# m2_to_apple.net
KiCad netlist of a schematic drawn in EAGLE
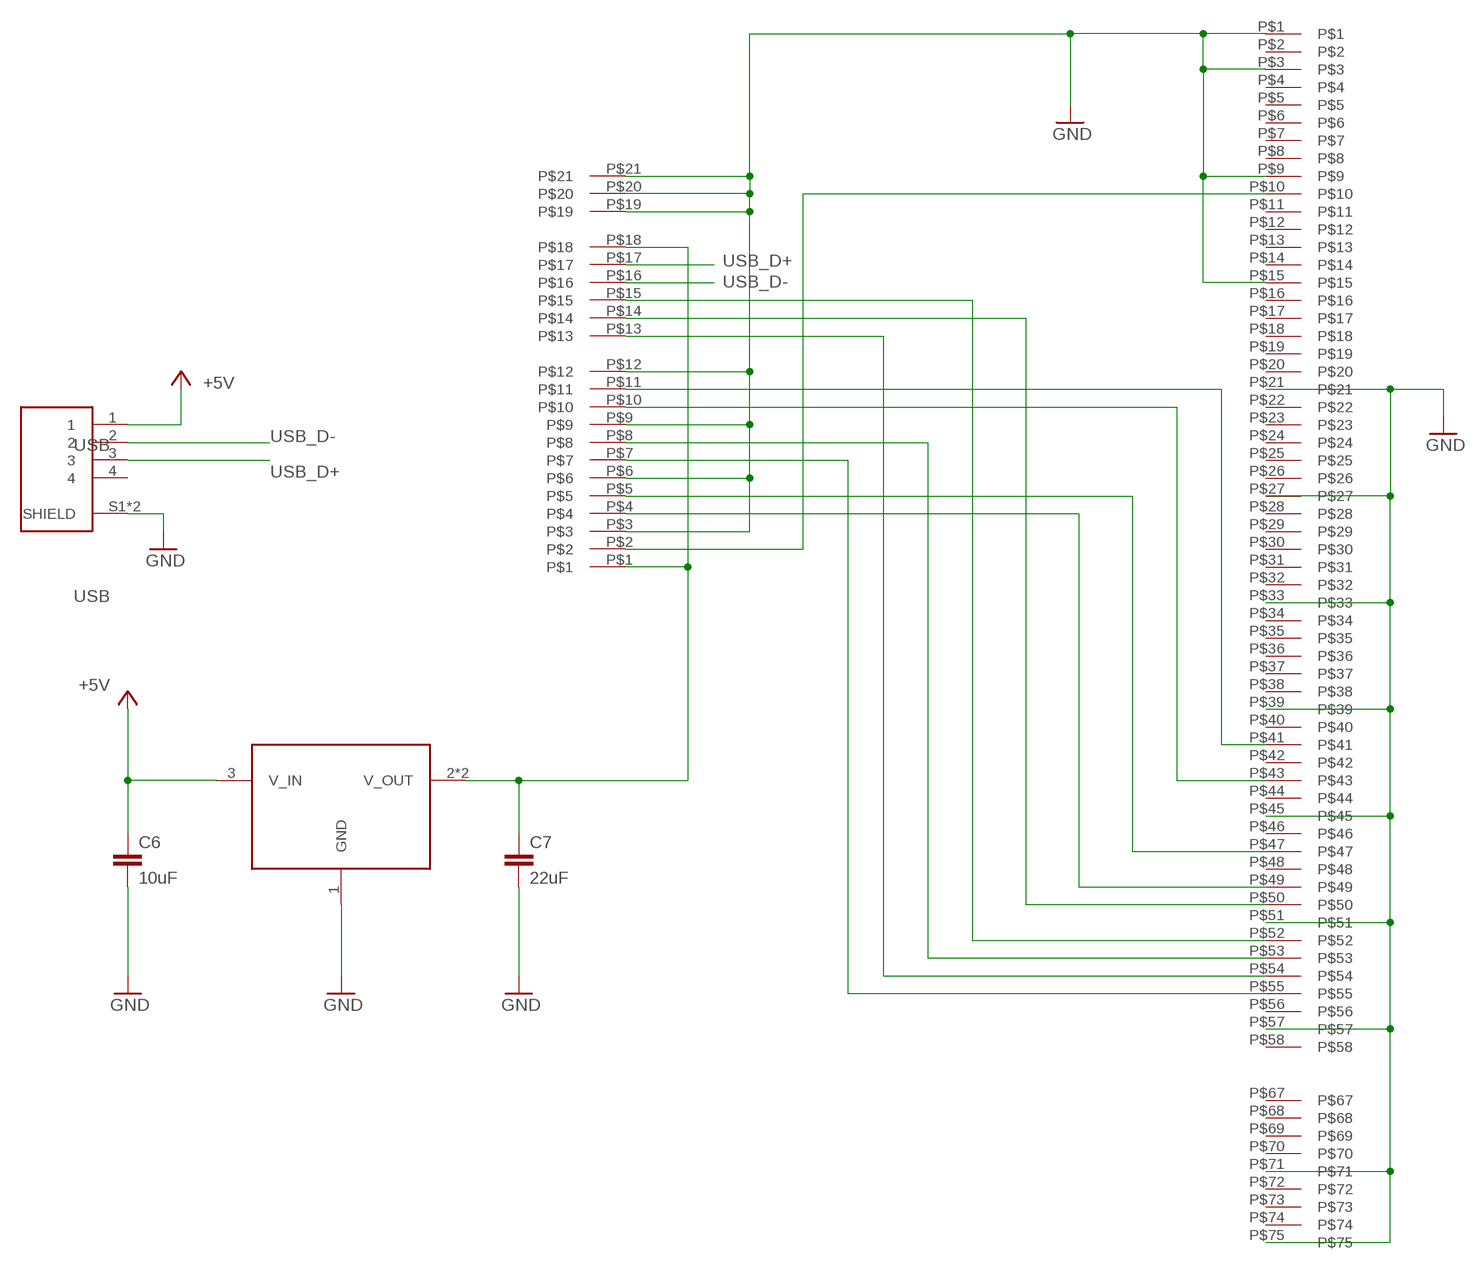
[diagram p0: schematic, sheet 1]

(export (version "E")
  (design (tool "Eeschema 10.0.6"))
  (components
    (comp (ref "C6")
      (value "10uF")
      (footprint "eagle-import:CAP_0603")
      (fields
        (field (name "DIGIKEY_PART_NUMBER") "399-7814-2-ND")
        (field (name "MANUFACTURER") "KEMET")
        (field (name "MPN") "C0603C100C5GACTU")
        (field (name "CREATED_BY") "PCBLayout.com")
      )
      (libsource (lib "eagle-import") (part "C0603C100C5GACTU"))
    )
    (comp (ref "C7")
      (value "22uF")
      (footprint "eagle-import:CAP_0603")
      (fields
        (field (name "DIGIKEY_PART_NUMBER") "399-7814-2-ND")
        (field (name "MANUFACTURER") "KEMET")
        (field (name "MPN") "C0603C100C5GACTU")
        (field (name "CREATED_BY") "PCBLayout.com")
      )
      (libsource (lib "eagle-import") (part "C0603C100C5GACTU"))
    )
    (comp (ref "U$1")
      (value "APPLE-WIFI")
      (footprint "eagle-import:APPLE_WIFI")
      (libsource (lib "eagle-import") (part "APPLE-WIFI"))
    )
    (comp (ref "U$2")
      (value "M.2_KEY_MSMD")
      (footprint "eagle-import:M.2_KEY_M")
      (libsource (lib "eagle-import") (part "M.2_KEY_MSMD"))
    )
    (comp (ref "U$3")
      (value "LM1117")
      (footprint "eagle-import:SOT223")
      (libsource (lib "eagle-import") (part "LM1117"))
    )
    (comp (ref "USB")
      (value "USB")
      (footprint "eagle-import:JST_1MM_4PINS")
      (libsource (lib "eagle-import") (part "JST_1MM_4PINS"))
    )
  )
  (nets
    (net (code "1") (name "+5V") (class "Default")
      (node (ref "C6") (pin "1") (pinfunction "1_1") (pintype "passive"))
      (node (ref "U$3") (pin "3") (pinfunction "V_IN_3") (pintype "input"))
      (node (ref "USB") (pin "1") (pinfunction "1_1") (pintype "passive"))
    )
    (net (code "2") (name "/USB_D+") (class "Default")
      (node (ref "U$1") (pin "P$17") (pinfunction "P$17_P$17") (pintype "bidirectional"))
      (node (ref "USB") (pin "3") (pinfunction "3_3") (pintype "passive"))
    )
    (net (code "3") (name "/USB_D-") (class "Default")
      (node (ref "U$1") (pin "P$16") (pinfunction "P$16_P$16") (pintype "bidirectional"))
      (node (ref "USB") (pin "2") (pinfunction "2_2") (pintype "passive"))
    )
    (net (code "4") (name "GND") (class "Default")
      (node (ref "C6") (pin "2") (pinfunction "2_2") (pintype "passive"))
      (node (ref "C7") (pin "2") (pinfunction "2_2") (pintype "passive"))
      (node (ref "U$1") (pin "P$12") (pinfunction "P$12_P$12") (pintype "bidirectional"))
      (node (ref "U$1") (pin "P$19") (pinfunction "P$19_P$19") (pintype "bidirectional"))
      (node (ref "U$1") (pin "P$20") (pinfunction "P$20_P$20") (pintype "bidirectional"))
      (node (ref "U$1") (pin "P$21") (pinfunction "P$21_P$21") (pintype "bidirectional"))
      (node (ref "U$1") (pin "P$3") (pinfunction "P$3_P$3") (pintype "bidirectional"))
      (node (ref "U$1") (pin "P$6") (pinfunction "P$6_P$6") (pintype "bidirectional"))
      (node (ref "U$1") (pin "P$9") (pinfunction "P$9_P$9") (pintype "bidirectional"))
      (node (ref "U$2") (pin "P$1") (pinfunction "P$1_P$1") (pintype "bidirectional"))
      (node (ref "U$2") (pin "P$15") (pinfunction "P$15_P$15") (pintype "bidirectional"))
      (node (ref "U$2") (pin "P$21") (pinfunction "P$21_P$21") (pintype "bidirectional"))
      (node (ref "U$2") (pin "P$27") (pinfunction "P$27_P$27") (pintype "bidirectional"))
      (node (ref "U$2") (pin "P$3") (pinfunction "P$3_P$3") (pintype "bidirectional"))
      (node (ref "U$2") (pin "P$33") (pinfunction "P$33_P$33") (pintype "bidirectional"))
      (node (ref "U$2") (pin "P$39") (pinfunction "P$39_P$39") (pintype "bidirectional"))
      (node (ref "U$2") (pin "P$45") (pinfunction "P$45_P$45") (pintype "bidirectional"))
      (node (ref "U$2") (pin "P$51") (pinfunction "P$51_P$51") (pintype "bidirectional"))
      (node (ref "U$2") (pin "P$57") (pinfunction "P$57_P$57") (pintype "bidirectional"))
      (node (ref "U$2") (pin "P$71") (pinfunction "P$71_P$71") (pintype "bidirectional"))
      (node (ref "U$2") (pin "P$75") (pinfunction "P$75_P$75") (pintype "bidirectional"))
      (node (ref "U$2") (pin "P$9") (pinfunction "P$9_P$9") (pintype "bidirectional"))
      (node (ref "U$3") (pin "1") (pinfunction "GND_1") (pintype "bidirectional"))
      (node (ref "USB") (pin "S1") (pinfunction "SHIELD_S1") (pintype "bidirectional"))
      (node (ref "USB") (pin "S2") (pinfunction "SHIELD_S2") (pintype "bidirectional"))
    )
    (net (code "5") (name "Net-(C7-Pad1)") (class "Default")
      (node (ref "C7") (pin "1") (pinfunction "1_1") (pintype "passive"))
      (node (ref "U$1") (pin "P$1") (pinfunction "P$1_P$1") (pintype "bidirectional"))
      (node (ref "U$1") (pin "P$18") (pinfunction "P$18_P$18") (pintype "bidirectional"))
      (node (ref "U$3") (pin "2") (pinfunction "V_OUT_2") (pintype "output"))
      (node (ref "U$3") (pin "4") (pinfunction "V_OUT_4") (pintype "output"))
    )
    (net (code "6") (name "Net-(U$1-PadP$2)") (class "Default")
      (node (ref "U$1") (pin "P$2") (pinfunction "P$2_P$2") (pintype "bidirectional"))
      (node (ref "U$2") (pin "P$10") (pinfunction "P$10_P$10") (pintype "bidirectional"))
    )
    (net (code "7") (name "Net-(U$1-PadP$4)") (class "Default")
      (node (ref "U$1") (pin "P$4") (pinfunction "P$4_P$4") (pintype "bidirectional"))
      (node (ref "U$2") (pin "P$49") (pinfunction "P$49_P$49") (pintype "bidirectional"))
    )
    (net (code "8") (name "Net-(U$1-PadP$5)") (class "Default")
      (node (ref "U$1") (pin "P$5") (pinfunction "P$5_P$5") (pintype "bidirectional"))
      (node (ref "U$2") (pin "P$47") (pinfunction "P$47_P$47") (pintype "bidirectional"))
    )
    (net (code "9") (name "Net-(U$1-PadP$7)") (class "Default")
      (node (ref "U$1") (pin "P$7") (pinfunction "P$7_P$7") (pintype "bidirectional"))
      (node (ref "U$2") (pin "P$55") (pinfunction "P$55_P$55") (pintype "bidirectional"))
    )
    (net (code "10") (name "Net-(U$1-PadP$8)") (class "Default")
      (node (ref "U$1") (pin "P$8") (pinfunction "P$8_P$8") (pintype "bidirectional"))
      (node (ref "U$2") (pin "P$53") (pinfunction "P$53_P$53") (pintype "bidirectional"))
    )
    (net (code "11") (name "Net-(U$1-PadP$10)") (class "Default")
      (node (ref "U$1") (pin "P$10") (pinfunction "P$10_P$10") (pintype "bidirectional"))
      (node (ref "U$2") (pin "P$43") (pinfunction "P$43_P$43") (pintype "bidirectional"))
    )
    (net (code "12") (name "Net-(U$1-PadP$11)") (class "Default")
      (node (ref "U$1") (pin "P$11") (pinfunction "P$11_P$11") (pintype "bidirectional"))
      (node (ref "U$2") (pin "P$41") (pinfunction "P$41_P$41") (pintype "bidirectional"))
    )
    (net (code "13") (name "Net-(U$1-PadP$13)") (class "Default")
      (node (ref "U$1") (pin "P$13") (pinfunction "P$13_P$13") (pintype "bidirectional"))
      (node (ref "U$2") (pin "P$54") (pinfunction "P$54_P$54") (pintype "bidirectional"))
    )
    (net (code "14") (name "Net-(U$1-PadP$14)") (class "Default")
      (node (ref "U$1") (pin "P$14") (pinfunction "P$14_P$14") (pintype "bidirectional"))
      (node (ref "U$2") (pin "P$50") (pinfunction "P$50_P$50") (pintype "bidirectional"))
    )
    (net (code "15") (name "Net-(U$1-PadP$15)") (class "Default")
      (node (ref "U$1") (pin "P$15") (pinfunction "P$15_P$15") (pintype "bidirectional"))
      (node (ref "U$2") (pin "P$52") (pinfunction "P$52_P$52") (pintype "bidirectional"))
    )
    (net (code "16") (name "unconnected-(U$2-PadP$2)") (class "Default")
      (node (ref "U$2") (pin "P$2") (pinfunction "P$2_P$2") (pintype "bidirectional"))
    )
    (net (code "17") (name "unconnected-(U$2-PadP$4)") (class "Default")
      (node (ref "U$2") (pin "P$4") (pinfunction "P$4_P$4") (pintype "bidirectional"))
    )
    (net (code "18") (name "unconnected-(U$2-PadP$5)") (class "Default")
      (node (ref "U$2") (pin "P$5") (pinfunction "P$5_P$5") (pintype "bidirectional"))
    )
    (net (code "19") (name "unconnected-(U$2-PadP$6)") (class "Default")
      (node (ref "U$2") (pin "P$6") (pinfunction "P$6_P$6") (pintype "bidirectional"))
    )
    (net (code "20") (name "unconnected-(U$2-PadP$7)") (class "Default")
      (node (ref "U$2") (pin "P$7") (pinfunction "P$7_P$7") (pintype "bidirectional"))
    )
    (net (code "21") (name "unconnected-(U$2-PadP$8)") (class "Default")
      (node (ref "U$2") (pin "P$8") (pinfunction "P$8_P$8") (pintype "bidirectional"))
    )
    (net (code "22") (name "unconnected-(U$2-PadP$11)") (class "Default")
      (node (ref "U$2") (pin "P$11") (pinfunction "P$11_P$11") (pintype "bidirectional"))
    )
    (net (code "23") (name "unconnected-(U$2-PadP$12)") (class "Default")
      (node (ref "U$2") (pin "P$12") (pinfunction "P$12_P$12") (pintype "bidirectional"))
    )
    (net (code "24") (name "unconnected-(U$2-PadP$13)") (class "Default")
      (node (ref "U$2") (pin "P$13") (pinfunction "P$13_P$13") (pintype "bidirectional"))
    )
    (net (code "25") (name "unconnected-(U$2-PadP$14)") (class "Default")
      (node (ref "U$2") (pin "P$14") (pinfunction "P$14_P$14") (pintype "bidirectional"))
    )
    (net (code "26") (name "unconnected-(U$2-PadP$16)") (class "Default")
      (node (ref "U$2") (pin "P$16") (pinfunction "P$16_P$16") (pintype "bidirectional"))
    )
    (net (code "27") (name "unconnected-(U$2-PadP$17)") (class "Default")
      (node (ref "U$2") (pin "P$17") (pinfunction "P$17_P$17") (pintype "bidirectional"))
    )
    (net (code "28") (name "unconnected-(U$2-PadP$18)") (class "Default")
      (node (ref "U$2") (pin "P$18") (pinfunction "P$18_P$18") (pintype "bidirectional"))
    )
    (net (code "29") (name "unconnected-(U$2-PadP$19)") (class "Default")
      (node (ref "U$2") (pin "P$19") (pinfunction "P$19_P$19") (pintype "bidirectional"))
    )
    (net (code "30") (name "unconnected-(U$2-PadP$20)") (class "Default")
      (node (ref "U$2") (pin "P$20") (pinfunction "P$20_P$20") (pintype "bidirectional"))
    )
    (net (code "31") (name "unconnected-(U$2-PadP$22)") (class "Default")
      (node (ref "U$2") (pin "P$22") (pinfunction "P$22_P$22") (pintype "bidirectional"))
    )
    (net (code "32") (name "unconnected-(U$2-PadP$23)") (class "Default")
      (node (ref "U$2") (pin "P$23") (pinfunction "P$23_P$23") (pintype "bidirectional"))
    )
    (net (code "33") (name "unconnected-(U$2-PadP$24)") (class "Default")
      (node (ref "U$2") (pin "P$24") (pinfunction "P$24_P$24") (pintype "bidirectional"))
    )
    (net (code "34") (name "unconnected-(U$2-PadP$25)") (class "Default")
      (node (ref "U$2") (pin "P$25") (pinfunction "P$25_P$25") (pintype "bidirectional"))
    )
    (net (code "35") (name "unconnected-(U$2-PadP$26)") (class "Default")
      (node (ref "U$2") (pin "P$26") (pinfunction "P$26_P$26") (pintype "bidirectional"))
    )
    (net (code "36") (name "unconnected-(U$2-PadP$28)") (class "Default")
      (node (ref "U$2") (pin "P$28") (pinfunction "P$28_P$28") (pintype "bidirectional"))
    )
    (net (code "37") (name "unconnected-(U$2-PadP$29)") (class "Default")
      (node (ref "U$2") (pin "P$29") (pinfunction "P$29_P$29") (pintype "bidirectional"))
    )
    (net (code "38") (name "unconnected-(U$2-PadP$30)") (class "Default")
      (node (ref "U$2") (pin "P$30") (pinfunction "P$30_P$30") (pintype "bidirectional"))
    )
    (net (code "39") (name "unconnected-(U$2-PadP$31)") (class "Default")
      (node (ref "U$2") (pin "P$31") (pinfunction "P$31_P$31") (pintype "bidirectional"))
    )
    (net (code "40") (name "unconnected-(U$2-PadP$32)") (class "Default")
      (node (ref "U$2") (pin "P$32") (pinfunction "P$32_P$32") (pintype "bidirectional"))
    )
    (net (code "41") (name "unconnected-(U$2-PadP$34)") (class "Default")
      (node (ref "U$2") (pin "P$34") (pinfunction "P$34_P$34") (pintype "bidirectional"))
    )
    (net (code "42") (name "unconnected-(U$2-PadP$35)") (class "Default")
      (node (ref "U$2") (pin "P$35") (pinfunction "P$35_P$35") (pintype "bidirectional"))
    )
    (net (code "43") (name "unconnected-(U$2-PadP$36)") (class "Default")
      (node (ref "U$2") (pin "P$36") (pinfunction "P$36_P$36") (pintype "bidirectional"))
    )
    (net (code "44") (name "unconnected-(U$2-PadP$37)") (class "Default")
      (node (ref "U$2") (pin "P$37") (pinfunction "P$37_P$37") (pintype "bidirectional"))
    )
    (net (code "45") (name "unconnected-(U$2-PadP$38)") (class "Default")
      (node (ref "U$2") (pin "P$38") (pinfunction "P$38_P$38") (pintype "bidirectional"))
    )
    (net (code "46") (name "unconnected-(U$2-PadP$40)") (class "Default")
      (node (ref "U$2") (pin "P$40") (pinfunction "P$40_P$40") (pintype "bidirectional"))
    )
    (net (code "47") (name "unconnected-(U$2-PadP$42)") (class "Default")
      (node (ref "U$2") (pin "P$42") (pinfunction "P$42_P$42") (pintype "bidirectional"))
    )
    (net (code "48") (name "unconnected-(U$2-PadP$44)") (class "Default")
      (node (ref "U$2") (pin "P$44") (pinfunction "P$44_P$44") (pintype "bidirectional"))
    )
    (net (code "49") (name "unconnected-(U$2-PadP$46)") (class "Default")
      (node (ref "U$2") (pin "P$46") (pinfunction "P$46_P$46") (pintype "bidirectional"))
    )
    (net (code "50") (name "unconnected-(U$2-PadP$48)") (class "Default")
      (node (ref "U$2") (pin "P$48") (pinfunction "P$48_P$48") (pintype "bidirectional"))
    )
    (net (code "51") (name "unconnected-(U$2-PadP$56)") (class "Default")
      (node (ref "U$2") (pin "P$56") (pinfunction "P$56_P$56") (pintype "bidirectional"))
    )
    (net (code "52") (name "unconnected-(U$2-PadP$58)") (class "Default")
      (node (ref "U$2") (pin "P$58") (pinfunction "P$58_P$58") (pintype "bidirectional"))
    )
    (net (code "53") (name "unconnected-(U$2-PadP$67)") (class "Default")
      (node (ref "U$2") (pin "P$67") (pinfunction "P$67_P$67") (pintype "bidirectional"))
    )
    (net (code "54") (name "unconnected-(U$2-PadP$68)") (class "Default")
      (node (ref "U$2") (pin "P$68") (pinfunction "P$68_P$68") (pintype "bidirectional"))
    )
    (net (code "55") (name "unconnected-(U$2-PadP$69)") (class "Default")
      (node (ref "U$2") (pin "P$69") (pinfunction "P$69_P$69") (pintype "bidirectional"))
    )
    (net (code "56") (name "unconnected-(U$2-PadP$70)") (class "Default")
      (node (ref "U$2") (pin "P$70") (pinfunction "P$70_P$70") (pintype "bidirectional"))
    )
    (net (code "57") (name "unconnected-(U$2-PadP$72)") (class "Default")
      (node (ref "U$2") (pin "P$72") (pinfunction "P$72_P$72") (pintype "bidirectional"))
    )
    (net (code "58") (name "unconnected-(U$2-PadP$73)") (class "Default")
      (node (ref "U$2") (pin "P$73") (pinfunction "P$73_P$73") (pintype "bidirectional"))
    )
    (net (code "59") (name "unconnected-(U$2-PadP$74)") (class "Default")
      (node (ref "U$2") (pin "P$74") (pinfunction "P$74_P$74") (pintype "bidirectional"))
    )
    (net (code "60") (name "unconnected-(USB-Pad4)") (class "Default")
      (node (ref "USB") (pin "4") (pinfunction "4_4") (pintype "passive"))
    )
  )
)
